# VM-MCU_v5_3.net
KiCad netlist of a schematic drawn in EAGLE
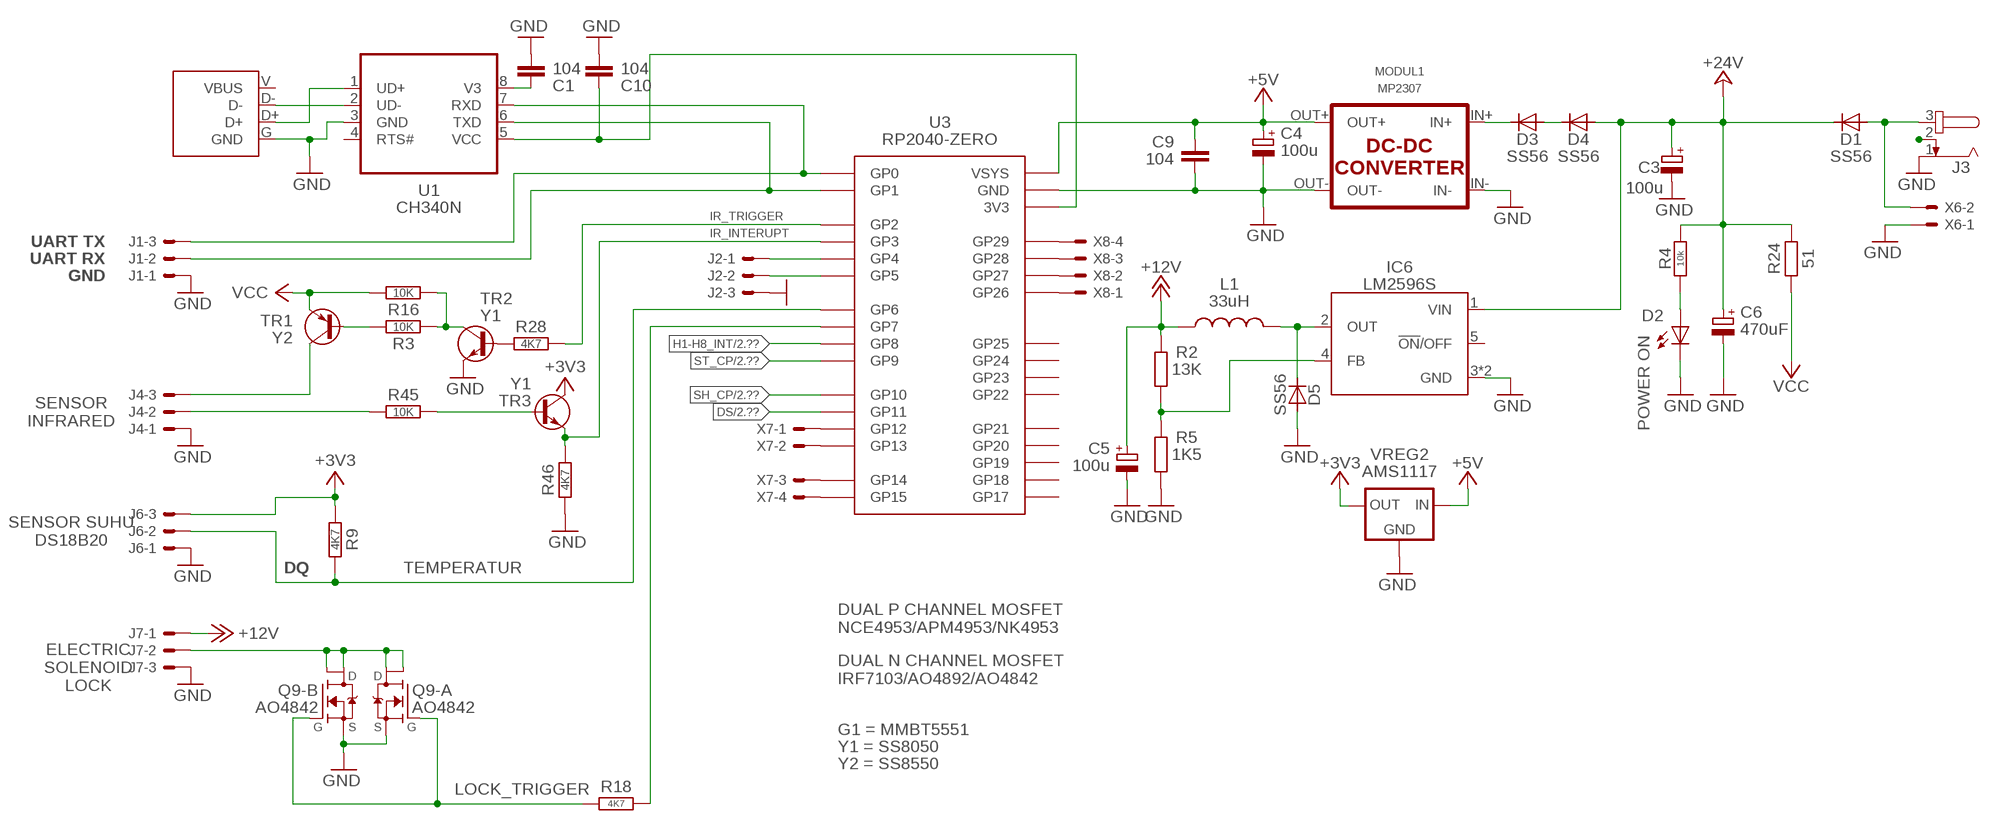
[diagram p0: schematic, sheet 1]
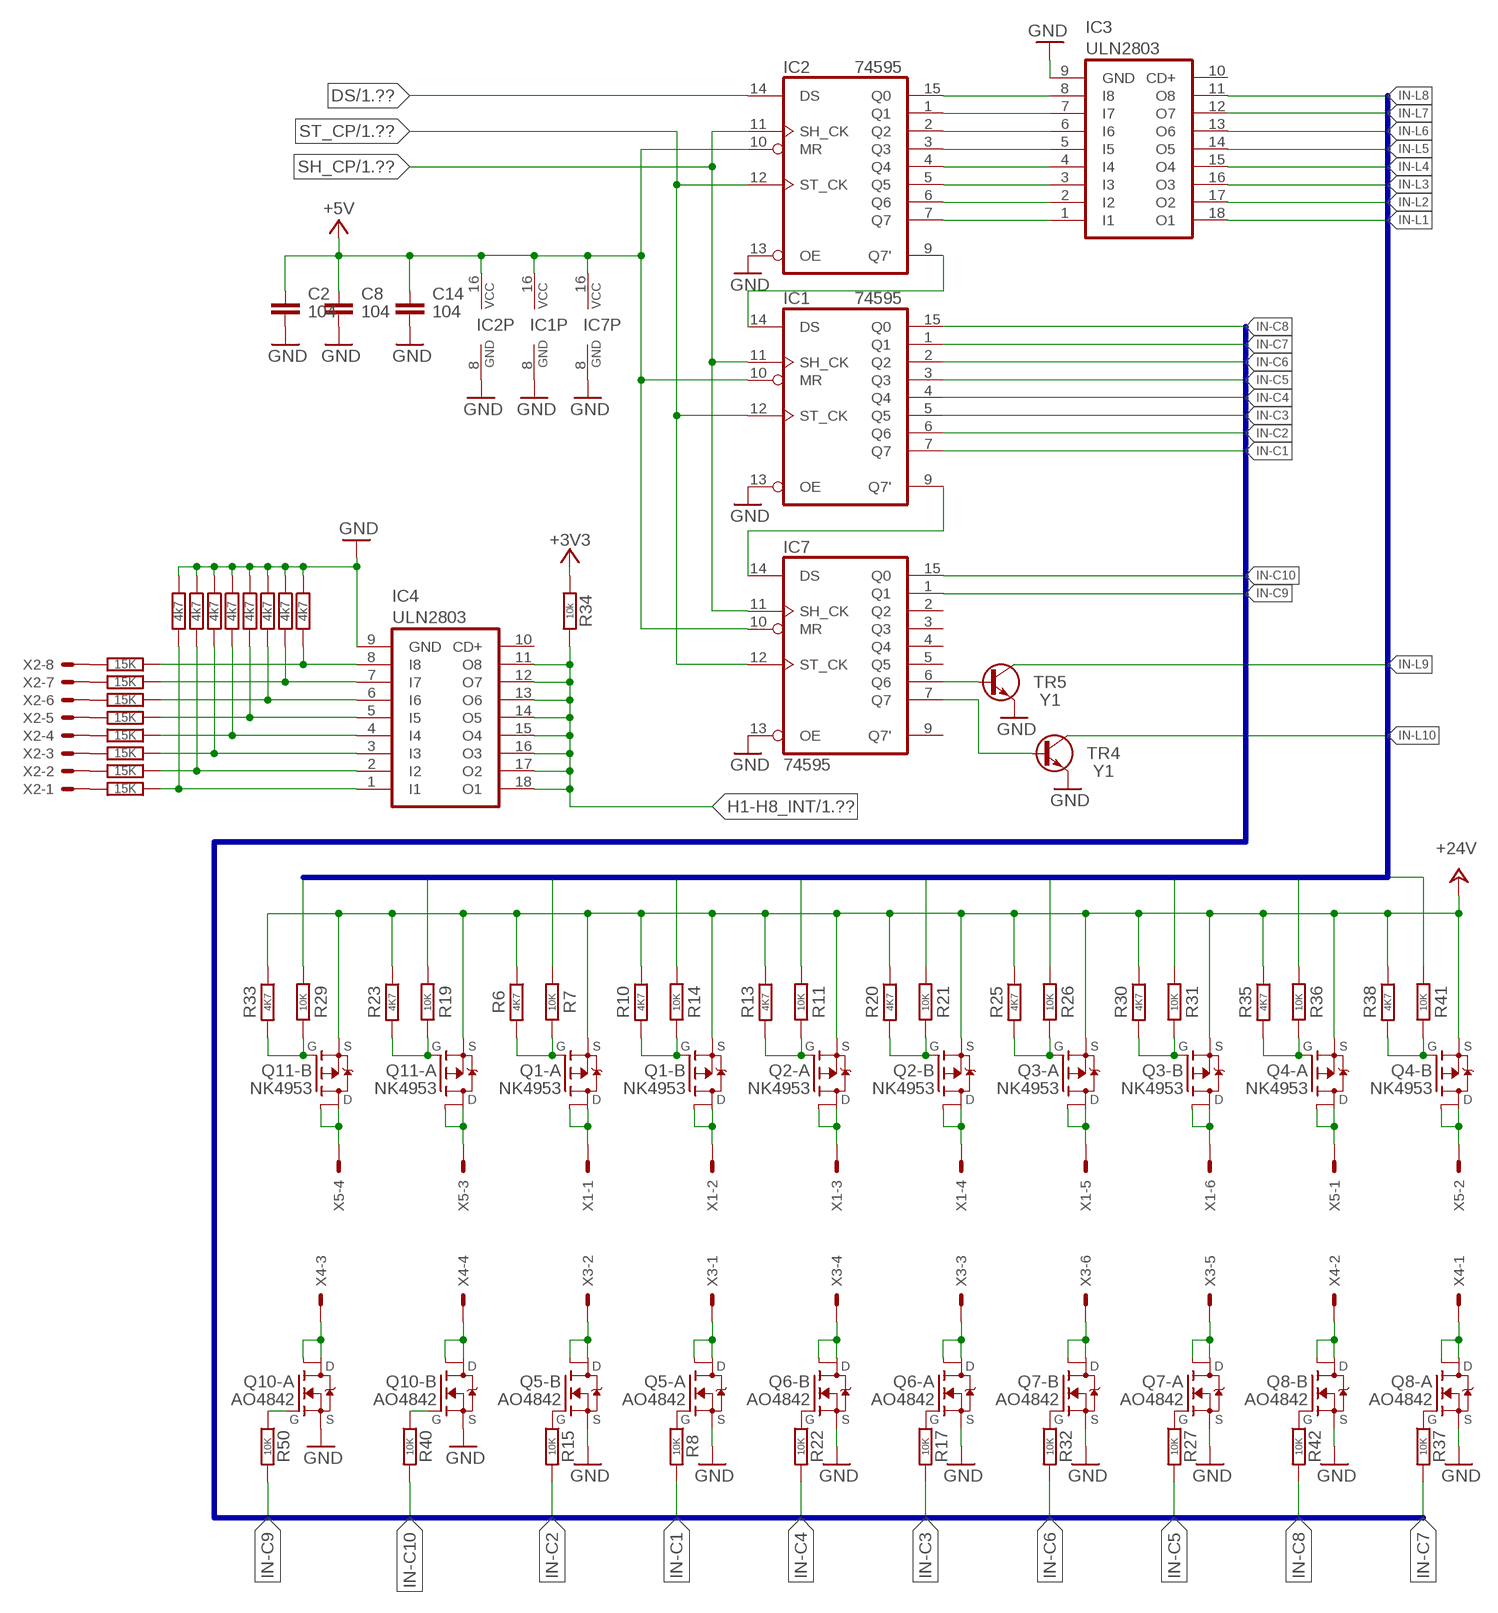
[diagram p1: schematic, sheet 2]

(export (version "E")
  (design (tool "Eeschema 10.0.6"))
  (components
    (comp (ref "C1")
      (value "104")
      (footprint "eagle-import:C1206")
      (libsource (lib "eagle-import") (part "CAP_SMD-C1206"))
    )
    (comp (ref "C3")
      (value "100u")
      (footprint "eagle-import:UD-6,3X7,7_NICHICON")
      (libsource (lib "eagle-import") (part "ELCO_UD-6,3X7,7"))
    )
    (comp (ref "C4")
      (value "100u")
      (footprint "eagle-import:UD-6,3X7,7_NICHICON")
      (libsource (lib "eagle-import") (part "ELCO_UD-6,3X7,7"))
    )
    (comp (ref "C5")
      (value "100u")
      (footprint "eagle-import:UD-6,3X7,7_NICHICON")
      (libsource (lib "eagle-import") (part "ELCO_UD-6,3X7,7"))
    )
    (comp (ref "C6")
      (value "470uF")
      (footprint "eagle-import:E5-10,5")
      (libsource (lib "eagle-import") (part "ELCO_E5-10.5"))
    )
    (comp (ref "C9")
      (value "104")
      (footprint "eagle-import:C1206")
      (libsource (lib "eagle-import") (part "CAP_SMD-C1206"))
    )
    (comp (ref "C10")
      (value "104")
      (footprint "eagle-import:C1206")
      (libsource (lib "eagle-import") (part "CAP_SMD-C1206"))
    )
    (comp (ref "D1")
      (value "SS56")
      (footprint "eagle-import:DO214AC")
      (libsource (lib "eagle-import") (part "DIODE_DO214AC"))
    )
    (comp (ref "D2")
      (value "POWER ON")
      (footprint "eagle-import:LED2835")
      (libsource (lib "eagle-import") (part "LED2835"))
    )
    (comp (ref "D3")
      (value "SS56")
      (footprint "eagle-import:DO214AC")
      (libsource (lib "eagle-import") (part "DIODE_DO214AC"))
    )
    (comp (ref "D4")
      (value "SS56")
      (footprint "eagle-import:DO214AC")
      (libsource (lib "eagle-import") (part "DIODE_DO214AC"))
    )
    (comp (ref "D5")
      (value "SS56")
      (footprint "eagle-import:DO214AC")
      (libsource (lib "eagle-import") (part "DIODE_DO214AC"))
    )
    (comp (ref "IC6")
      (value "LM2596S")
      (footprint "eagle-import:TO263-5")
      (fields (field (name "MF") "NATIONAL SEMICONDUCTOR") (field (name "MPN") "LM2596S-ADJ/NOPB"))
      (libsource (lib "eagle-import") (part "LM2596S"))
    )
    (comp (ref "J1")
      (value "SOKET-3P_KF2510-2.54")
      (footprint "eagle-import:KF2510-3P")
      (libsource (lib "eagle-import") (part "SOKET-3P_KF2510-2.54"))
    )
    (comp (ref "J2")
      (value "SOKET-3P_JST-XH-2.54")
      (footprint "eagle-import:3P-JST-XH")
      (libsource (lib "eagle-import") (part "SOKET-3P_JST-XH-2.54"))
    )
    (comp (ref "J3")
      (value "JACK-DC_5.5X2.1MM")
      (footprint "eagle-import:DC-5.5X2.1")
      (libsource (lib "eagle-import") (part "JACK-DC_5.5X2.1MM"))
    )
    (comp (ref "J4")
      (value "SOKET-3P_MOLEX-3.96")
      (footprint "eagle-import:3P-MOLEX")
      (fields (field (name "MF") "MOLEX"))
      (libsource (lib "eagle-import") (part "SOKET-3P_MOLEX-3.96"))
    )
    (comp (ref "J6")
      (value "SOKET-3P_KF2510-2.54")
      (footprint "eagle-import:KF2510-3P")
      (libsource (lib "eagle-import") (part "SOKET-3P_KF2510-2.54"))
    )
    (comp (ref "J7")
      (value "SOKET-3P_KF2510-2.54")
      (footprint "eagle-import:KF2510-3P")
      (libsource (lib "eagle-import") (part "SOKET-3P_KF2510-2.54"))
    )
    (comp (ref "L1")
      (value "33uH")
      (footprint "eagle-import:CDRH104")
      (libsource (lib "eagle-import") (part "INDUKTOR10X10"))
    )
    (comp (ref "MODUL1")
      (value "MP2307")
      (footprint "eagle-import:MP2307")
      (libsource (lib "eagle-import") (part "MINI360-MP2307MP2307-PTH"))
    )
    (comp (ref "Q9")
      (value "AO4842")
      (footprint "eagle-import:SO-8")
      (libsource (lib "eagle-import") (part "DUALFET-N_N+NAO4892"))
    )
    (comp (ref "R2")
      (value "13K")
      (footprint "eagle-import:R1206")
      (libsource (lib "eagle-import") (part "VM-MCU_RESISTOR_1206"))
    )
    (comp (ref "R3")
      (value "10K")
      (footprint "eagle-import:R1206")
      (libsource (lib "eagle-import") (part "VM-MCU_RESISTOR_1206"))
    )
    (comp (ref "R4")
      (value "10k")
      (footprint "eagle-import:R1206")
      (libsource (lib "eagle-import") (part "RESISTOR_1206"))
    )
    (comp (ref "R5")
      (value "1K5")
      (footprint "eagle-import:R1206")
      (libsource (lib "eagle-import") (part "VM-MCU_RESISTOR_1206"))
    )
    (comp (ref "R9")
      (value "4K7")
      (footprint "eagle-import:R1206")
      (libsource (lib "eagle-import") (part "VM-MCU_RESISTOR_1206"))
    )
    (comp (ref "R16")
      (value "10K")
      (footprint "eagle-import:R1206")
      (libsource (lib "eagle-import") (part "VM-MCU_RESISTOR_1206"))
    )
    (comp (ref "R18")
      (value "4K7")
      (footprint "eagle-import:R1206")
      (libsource (lib "eagle-import") (part "VM-MCU_RESISTOR_1206"))
    )
    (comp (ref "R24")
      (value "51")
      (footprint "eagle-import:R2512")
      (libsource (lib "eagle-import") (part "RESISTOR_2512"))
    )
    (comp (ref "R28")
      (value "4K7")
      (footprint "eagle-import:R1206")
      (libsource (lib "eagle-import") (part "VM-MCU_RESISTOR_1206"))
    )
    (comp (ref "R45")
      (value "10K")
      (footprint "eagle-import:R1206")
      (libsource (lib "eagle-import") (part "RESISTOR_1206"))
    )
    (comp (ref "R46")
      (value "4K7")
      (footprint "eagle-import:R1206")
      (libsource (lib "eagle-import") (part "VM-MCU_RESISTOR_1206"))
    )
    (comp (ref "TR1")
      (value "Y2")
      (footprint "eagle-import:SOT23-BEC")
      (libsource (lib "eagle-import") (part "BJT-PNP_SOT23-BCE"))
    )
    (comp (ref "TR2")
      (value "Y1")
      (footprint "eagle-import:SOT23-BEC")
      (libsource (lib "eagle-import") (part "BJT-NPN_SOT23-BEC"))
    )
    (comp (ref "TR3")
      (value "Y1")
      (footprint "eagle-import:SOT23-BEC")
      (libsource (lib "eagle-import") (part "BJT-NPN_SOT23-BEC"))
    )
    (comp (ref "U$3")
      (value "USB-C_BREAKOUT_")
      (footprint "eagle-import:USB-C_4P")
      (libsource (lib "eagle-import") (part "USB-C_BREAKOUT_"))
    )
    (comp (ref "U1")
      (value "CH340N")
      (footprint "eagle-import:SO-8")
      (libsource (lib "eagle-import") (part "CH340N"))
    )
    (comp (ref "U3")
      (value "RP2040-ZERO")
      (footprint "eagle-import:PICO-ZERO")
      (libsource (lib "eagle-import") (part "RASPBERRY-PICO-ZERO_"))
    )
    (comp (ref "VREG2")
      (value "AMS1117")
      (footprint "eagle-import:SOT223")
      (libsource (lib "eagle-import") (part "78XXX_SOT223"))
    )
    (comp (ref "X6")
      (value "SOKET-2P_MOLEX-3.96")
      (footprint "eagle-import:2P-MOLEX")
      (fields (field (name "MF") "MOLEX"))
      (libsource (lib "eagle-import") (part "SOKET-2P_MOLEX-3.96"))
    )
    (comp (ref "X7")
      (value "SOKET-4P_JST-XH-2.54")
      (footprint "eagle-import:4P-JST-XH")
      (libsource (lib "eagle-import") (part "SOKET-4P_JST-XH-2.54"))
    )
    (comp (ref "X8")
      (value "SOKET-4P_JST-XH-2.54")
      (footprint "eagle-import:4P-JST-XH")
      (libsource (lib "eagle-import") (part "SOKET-4P_JST-XH-2.54"))
    )
    (comp (ref "C2")
      (value "104")
      (footprint "eagle-import:C1206")
      (libsource (lib "eagle-import") (part "CAP_SMD-C1206"))
    )
    (comp (ref "C8")
      (value "104")
      (footprint "eagle-import:C1206")
      (libsource (lib "eagle-import") (part "CAP_SMD-C1206"))
    )
    (comp (ref "C14")
      (value "104")
      (footprint "eagle-import:C1206")
      (libsource (lib "eagle-import") (part "CAP_SMD-C1206"))
    )
    (comp (ref "IC1")
      (value "74595")
      (footprint "eagle-import:SO16")
      (libsource (lib "eagle-import") (part "74595"))
    )
    (comp (ref "IC2")
      (value "74595")
      (footprint "eagle-import:SO16")
      (libsource (lib "eagle-import") (part "74595"))
    )
    (comp (ref "IC3")
      (value "ULN2803")
      (footprint "eagle-import:SO18W")
      (libsource (lib "eagle-import") (part "ULN2805ASO18"))
    )
    (comp (ref "IC4")
      (value "ULN2803")
      (footprint "eagle-import:SO18W")
      (libsource (lib "eagle-import") (part "ULN2805ASO18"))
    )
    (comp (ref "IC7")
      (value "74595")
      (footprint "eagle-import:SO16")
      (libsource (lib "eagle-import") (part "74595"))
    )
    (comp (ref "Q1")
      (value "NK4953")
      (footprint "eagle-import:SO-8")
      (libsource (lib "eagle-import") (part "DUALFET-P_P+PNCE4953"))
    )
    (comp (ref "Q2")
      (value "NK4953")
      (footprint "eagle-import:SO-8")
      (libsource (lib "eagle-import") (part "DUALFET-P_P+PNCE4953"))
    )
    (comp (ref "Q3")
      (value "NK4953")
      (footprint "eagle-import:SO-8")
      (libsource (lib "eagle-import") (part "DUALFET-P_P+PNCE4953"))
    )
    (comp (ref "Q4")
      (value "NK4953")
      (footprint "eagle-import:SO-8")
      (libsource (lib "eagle-import") (part "DUALFET-P_P+PNCE4953"))
    )
    (comp (ref "Q5")
      (value "AO4842")
      (footprint "eagle-import:SO-8")
      (libsource (lib "eagle-import") (part "DUALFET-N_N+NAO4892"))
    )
    (comp (ref "Q6")
      (value "AO4842")
      (footprint "eagle-import:SO-8")
      (libsource (lib "eagle-import") (part "DUALFET-N_N+NAO4892"))
    )
    (comp (ref "Q7")
      (value "AO4842")
      (footprint "eagle-import:SO-8")
      (libsource (lib "eagle-import") (part "DUALFET-N_N+NAO4892"))
    )
    (comp (ref "Q8")
      (value "AO4842")
      (footprint "eagle-import:SO-8")
      (libsource (lib "eagle-import") (part "DUALFET-N_N+NAO4892"))
    )
    (comp (ref "Q10")
      (value "AO4842")
      (footprint "eagle-import:SO-8")
      (libsource (lib "eagle-import") (part "DUALFET-N_N+NAO4892"))
    )
    (comp (ref "Q11")
      (value "NK4953")
      (footprint "eagle-import:SO-8")
      (libsource (lib "eagle-import") (part "DUALFET-P_P+PNCE4953"))
    )
    (comp (ref "R1")
      (value "15K")
      (footprint "eagle-import:R0805")
      (libsource (lib "eagle-import") (part "RESISTOR_0805"))
    )
    (comp (ref "R6")
      (value "4K7")
      (footprint "eagle-import:R1206")
      (libsource (lib "eagle-import") (part "RESISTOR_1206"))
    )
    (comp (ref "R7")
      (value "10K")
      (footprint "eagle-import:R1206")
      (libsource (lib "eagle-import") (part "RESISTOR_1206"))
    )
    (comp (ref "R8")
      (value "10K")
      (footprint "eagle-import:R1206")
      (libsource (lib "eagle-import") (part "RESISTOR_1206"))
    )
    (comp (ref "R10")
      (value "4K7")
      (footprint "eagle-import:R1206")
      (libsource (lib "eagle-import") (part "RESISTOR_1206"))
    )
    (comp (ref "R11")
      (value "10K")
      (footprint "eagle-import:R1206")
      (libsource (lib "eagle-import") (part "RESISTOR_1206"))
    )
    (comp (ref "R12")
      (value "15K")
      (footprint "eagle-import:R0805")
      (libsource (lib "eagle-import") (part "RESISTOR_0805"))
    )
    (comp (ref "R13")
      (value "4K7")
      (footprint "eagle-import:R1206")
      (libsource (lib "eagle-import") (part "RESISTOR_1206"))
    )
    (comp (ref "R14")
      (value "10K")
      (footprint "eagle-import:R1206")
      (libsource (lib "eagle-import") (part "RESISTOR_1206"))
    )
    (comp (ref "R15")
      (value "10K")
      (footprint "eagle-import:R1206")
      (libsource (lib "eagle-import") (part "RESISTOR_1206"))
    )
    (comp (ref "R17")
      (value "10K")
      (footprint "eagle-import:R1206")
      (libsource (lib "eagle-import") (part "RESISTOR_1206"))
    )
    (comp (ref "R19")
      (value "10K")
      (footprint "eagle-import:R1206")
      (libsource (lib "eagle-import") (part "RESISTOR_1206"))
    )
    (comp (ref "R20")
      (value "4K7")
      (footprint "eagle-import:R1206")
      (libsource (lib "eagle-import") (part "RESISTOR_1206"))
    )
    (comp (ref "R21")
      (value "10K")
      (footprint "eagle-import:R1206")
      (libsource (lib "eagle-import") (part "RESISTOR_1206"))
    )
    (comp (ref "R22")
      (value "10K")
      (footprint "eagle-import:R1206")
      (libsource (lib "eagle-import") (part "RESISTOR_1206"))
    )
    (comp (ref "R23")
      (value "4K7")
      (footprint "eagle-import:R1206")
      (libsource (lib "eagle-import") (part "RESISTOR_1206"))
    )
    (comp (ref "R25")
      (value "4K7")
      (footprint "eagle-import:R1206")
      (libsource (lib "eagle-import") (part "RESISTOR_1206"))
    )
    (comp (ref "R26")
      (value "10K")
      (footprint "eagle-import:R1206")
      (libsource (lib "eagle-import") (part "RESISTOR_1206"))
    )
    (comp (ref "R27")
      (value "10K")
      (footprint "eagle-import:R1206")
      (libsource (lib "eagle-import") (part "RESISTOR_1206"))
    )
    (comp (ref "R29")
      (value "10K")
      (footprint "eagle-import:R1206")
      (libsource (lib "eagle-import") (part "RESISTOR_1206"))
    )
    (comp (ref "R30")
      (value "4K7")
      (footprint "eagle-import:R1206")
      (libsource (lib "eagle-import") (part "RESISTOR_1206"))
    )
    (comp (ref "R31")
      (value "10K")
      (footprint "eagle-import:R1206")
      (libsource (lib "eagle-import") (part "RESISTOR_1206"))
    )
    (comp (ref "R32")
      (value "10K")
      (footprint "eagle-import:R1206")
      (libsource (lib "eagle-import") (part "RESISTOR_1206"))
    )
    (comp (ref "R33")
      (value "4K7")
      (footprint "eagle-import:R1206")
      (libsource (lib "eagle-import") (part "RESISTOR_1206"))
    )
    (comp (ref "R34")
      (value "10k")
      (footprint "eagle-import:R1206")
      (libsource (lib "eagle-import") (part "RESISTOR_1206"))
    )
    (comp (ref "R35")
      (value "4K7")
      (footprint "eagle-import:R1206")
      (libsource (lib "eagle-import") (part "RESISTOR_1206"))
    )
    (comp (ref "R36")
      (value "10K")
      (footprint "eagle-import:R1206")
      (libsource (lib "eagle-import") (part "RESISTOR_1206"))
    )
    (comp (ref "R37")
      (value "10K")
      (footprint "eagle-import:R1206")
      (libsource (lib "eagle-import") (part "RESISTOR_1206"))
    )
    (comp (ref "R38")
      (value "4K7")
      (footprint "eagle-import:R1206")
      (libsource (lib "eagle-import") (part "RESISTOR_1206"))
    )
    (comp (ref "R39")
      (value "15K")
      (footprint "eagle-import:R0805")
      (libsource (lib "eagle-import") (part "RESISTOR_0805"))
    )
    (comp (ref "R40")
      (value "10K")
      (footprint "eagle-import:R1206")
      (libsource (lib "eagle-import") (part "RESISTOR_1206"))
    )
    (comp (ref "R41")
      (value "10K")
      (footprint "eagle-import:R1206")
      (libsource (lib "eagle-import") (part "RESISTOR_1206"))
    )
    (comp (ref "R42")
      (value "10K")
      (footprint "eagle-import:R1206")
      (libsource (lib "eagle-import") (part "RESISTOR_1206"))
    )
    (comp (ref "R43")
      (value "15K")
      (footprint "eagle-import:R0805")
      (libsource (lib "eagle-import") (part "RESISTOR_0805"))
    )
    (comp (ref "R44")
      (value "15K")
      (footprint "eagle-import:R0805")
      (libsource (lib "eagle-import") (part "RESISTOR_0805"))
    )
    (comp (ref "R47")
      (value "15K")
      (footprint "eagle-import:R0805")
      (libsource (lib "eagle-import") (part "RESISTOR_0805"))
    )
    (comp (ref "R48")
      (value "15K")
      (footprint "eagle-import:R0805")
      (libsource (lib "eagle-import") (part "RESISTOR_0805"))
    )
    (comp (ref "R49")
      (value "15K")
      (footprint "eagle-import:R0805")
      (libsource (lib "eagle-import") (part "RESISTOR_0805"))
    )
    (comp (ref "R50")
      (value "10K")
      (footprint "eagle-import:R1206")
      (libsource (lib "eagle-import") (part "RESISTOR_1206"))
    )
    (comp (ref "R51")
      (value "4k7")
      (footprint "eagle-import:R0805")
      (libsource (lib "eagle-import") (part "RESISTOR_0805"))
    )
    (comp (ref "R52")
      (value "4k7")
      (footprint "eagle-import:R0805")
      (libsource (lib "eagle-import") (part "RESISTOR_0805"))
    )
    (comp (ref "R53")
      (value "4k7")
      (footprint "eagle-import:R0805")
      (libsource (lib "eagle-import") (part "RESISTOR_0805"))
    )
    (comp (ref "R54")
      (value "4k7")
      (footprint "eagle-import:R0805")
      (libsource (lib "eagle-import") (part "RESISTOR_0805"))
    )
    (comp (ref "R55")
      (value "4k7")
      (footprint "eagle-import:R0805")
      (libsource (lib "eagle-import") (part "RESISTOR_0805"))
    )
    (comp (ref "R56")
      (value "4k7")
      (footprint "eagle-import:R0805")
      (libsource (lib "eagle-import") (part "RESISTOR_0805"))
    )
    (comp (ref "R57")
      (value "4k7")
      (footprint "eagle-import:R0805")
      (libsource (lib "eagle-import") (part "RESISTOR_0805"))
    )
    (comp (ref "R58")
      (value "4k7")
      (footprint "eagle-import:R0805")
      (libsource (lib "eagle-import") (part "RESISTOR_0805"))
    )
    (comp (ref "TR4")
      (value "Y1")
      (footprint "eagle-import:SOT23-BEC")
      (libsource (lib "eagle-import") (part "BJT-NPN_SOT23-BEC"))
    )
    (comp (ref "TR5")
      (value "Y1")
      (footprint "eagle-import:SOT23-BEC")
      (libsource (lib "eagle-import") (part "BJT-NPN_SOT23-BEC"))
    )
    (comp (ref "X1")
      (value "SOKET-6P_MOLEX-3.96")
      (footprint "eagle-import:6P-MOLEX")
      (fields (field (name "MF") "MOLEX"))
      (libsource (lib "eagle-import") (part "SOKET-6P_MOLEX-3.96"))
    )
    (comp (ref "X2")
      (value "SOKET-8P_MOLEX-3.96")
      (footprint "eagle-import:8P-MOLEX")
      (fields (field (name "MF") "MOLEX"))
      (libsource (lib "eagle-import") (part "SOKET-8P_MOLEX-3.96"))
    )
    (comp (ref "X3")
      (value "SOKET-6P_MOLEX-3.96")
      (footprint "eagle-import:6P-MOLEX")
      (fields (field (name "MF") "MOLEX"))
      (libsource (lib "eagle-import") (part "SOKET-6P_MOLEX-3.96"))
    )
    (comp (ref "X4")
      (value "SOKET-4P_MOLEX-3.96")
      (footprint "eagle-import:4P-MOLEX")
      (fields (field (name "MF") "MOLEX"))
      (libsource (lib "eagle-import") (part "SOKET-4P_MOLEX-3.96"))
    )
    (comp (ref "X5")
      (value "SOKET-4P_MOLEX-3.96")
      (footprint "eagle-import:4P-MOLEX")
      (fields (field (name "MF") "MOLEX"))
      (libsource (lib "eagle-import") (part "SOKET-4P_MOLEX-3.96"))
    )
  )
  (nets
    (net (code "1") (name "+3V3") (class "Default")
      (node (ref "J6") (pin "3") (pinfunction "S_3") (pintype "passive"))
      (node (ref "R34") (pin "2") (pinfunction "2_2") (pintype "passive"))
      (node (ref "R9") (pin "1") (pinfunction "1_1") (pintype "passive"))
      (node (ref "TR3") (pin "C") (pinfunction "C_C") (pintype "passive"))
      (node (ref "VREG2") (pin "4") (pinfunction "OUT_4") (pintype "passive"))
    )
    (net (code "2") (name "+5V") (class "Default")
      (node (ref "C14") (pin "1") (pinfunction "1_1") (pintype "passive"))
      (node (ref "C2") (pin "1") (pinfunction "1_1") (pintype "passive"))
      (node (ref "C4") (pin "+") (pinfunction "+_+") (pintype "passive"))
      (node (ref "C8") (pin "1") (pinfunction "1_1") (pintype "passive"))
      (node (ref "C9") (pin "1") (pinfunction "1_1") (pintype "passive"))
      (node (ref "IC1") (pin "10") (pinfunction "MR_10") (pintype "input"))
      (node (ref "IC1") (pin "16") (pinfunction "VCC_16") (pintype "power_in"))
      (node (ref "IC2") (pin "10") (pinfunction "MR_10") (pintype "input"))
      (node (ref "IC2") (pin "16") (pinfunction "VCC_16") (pintype "power_in"))
      (node (ref "IC7") (pin "10") (pinfunction "MR_10") (pintype "input"))
      (node (ref "IC7") (pin "16") (pinfunction "VCC_16") (pintype "power_in"))
      (node (ref "MODUL1") (pin "OUT+") (pinfunction "OUT+_OUT+") (pintype "bidirectional"))
      (node (ref "U3") (pin "5V") (pinfunction "VSYS_5V") (pintype "power_in"))
      (node (ref "VREG2") (pin "3") (pinfunction "IN_3") (pintype "input"))
    )
    (net (code "3") (name "+12V") (class "Default")
      (node (ref "C5") (pin "+") (pinfunction "+_+") (pintype "passive"))
      (node (ref "J7") (pin "1") (pinfunction "S_1") (pintype "passive"))
      (node (ref "L1") (pin "1") (pinfunction "1_1") (pintype "passive"))
      (node (ref "R2") (pin "1") (pinfunction "1_1") (pintype "passive"))
    )
    (net (code "4") (name "+24V") (class "Default")
      (node (ref "C3") (pin "+") (pinfunction "+_+") (pintype "passive"))
      (node (ref "C6") (pin "+") (pinfunction "+_+") (pintype "passive"))
      (node (ref "D1") (pin "C") (pinfunction "C_C") (pintype "passive"))
      (node (ref "D4") (pin "A") (pinfunction "A_A") (pintype "passive"))
      (node (ref "IC6") (pin "1") (pinfunction "VIN_1") (pintype "input"))
      (node (ref "Q1") (pin "1") (pinfunction "S_1") (pintype "passive"))
      (node (ref "Q1") (pin "3") (pinfunction "S_3") (pintype "passive"))
      (node (ref "Q11") (pin "1") (pinfunction "S_1") (pintype "passive"))
      (node (ref "Q11") (pin "3") (pinfunction "S_3") (pintype "passive"))
      (node (ref "Q2") (pin "1") (pinfunction "S_1") (pintype "passive"))
      (node (ref "Q2") (pin "3") (pinfunction "S_3") (pintype "passive"))
      (node (ref "Q3") (pin "1") (pinfunction "S_1") (pintype "passive"))
      (node (ref "Q3") (pin "3") (pinfunction "S_3") (pintype "passive"))
      (node (ref "Q4") (pin "1") (pinfunction "S_1") (pintype "passive"))
      (node (ref "Q4") (pin "3") (pinfunction "S_3") (pintype "passive"))
      (node (ref "R10") (pin "1") (pinfunction "1_1") (pintype "passive"))
      (node (ref "R13") (pin "1") (pinfunction "1_1") (pintype "passive"))
      (node (ref "R20") (pin "1") (pinfunction "1_1") (pintype "passive"))
      (node (ref "R23") (pin "1") (pinfunction "1_1") (pintype "passive"))
      (node (ref "R24") (pin "2") (pinfunction "2_2") (pintype "passive"))
      (node (ref "R25") (pin "1") (pinfunction "1_1") (pintype "passive"))
      (node (ref "R30") (pin "1") (pinfunction "1_1") (pintype "passive"))
      (node (ref "R33") (pin "1") (pinfunction "1_1") (pintype "passive"))
      (node (ref "R35") (pin "1") (pinfunction "1_1") (pintype "passive"))
      (node (ref "R38") (pin "1") (pinfunction "1_1") (pintype "passive"))
      (node (ref "R4") (pin "2") (pinfunction "2_2") (pintype "passive"))
      (node (ref "R6") (pin "1") (pinfunction "1_1") (pintype "passive"))
    )
    (net (code "5") (name "DS") (class "Default")
      (node (ref "IC2") (pin "14") (pinfunction "DS_14") (pintype "input"))
      (node (ref "U3") (pin "P11") (pinfunction "GP11_P11") (pintype "bidirectional"))
    )
    (net (code "6") (name "GND") (class "Default")
      (node (ref "C1") (pin "2") (pinfunction "2_2") (pintype "passive"))
      (node (ref "C10") (pin "2") (pinfunction "2_2") (pintype "passive"))
      (node (ref "C14") (pin "2") (pinfunction "2_2") (pintype "passive"))
      (node (ref "C2") (pin "2") (pinfunction "2_2") (pintype "passive"))
      (node (ref "C3") (pin "-") (pinfunction "-_-") (pintype "passive"))
      (node (ref "C4") (pin "-") (pinfunction "-_-") (pintype "passive"))
      (node (ref "C5") (pin "-") (pinfunction "-_-") (pintype "passive"))
      (node (ref "C6") (pin "-") (pinfunction "-_-") (pintype "passive"))
      (node (ref "C8") (pin "2") (pinfunction "2_2") (pintype "passive"))
      (node (ref "C9") (pin "2") (pinfunction "2_2") (pintype "passive"))
      (node (ref "D2") (pin "C") (pinfunction "C_C") (pintype "passive"))
      (node (ref "D5") (pin "A") (pinfunction "A_A") (pintype "passive"))
      (node (ref "IC1") (pin "13") (pinfunction "OE_13") (pintype "input"))
      (node (ref "IC1") (pin "8") (pinfunction "GND_8") (pintype "power_in"))
      (node (ref "IC2") (pin "13") (pinfunction "OE_13") (pintype "input"))
      (node (ref "IC2") (pin "8") (pinfunction "GND_8") (pintype "power_in"))
      (node (ref "IC3") (pin "9") (pinfunction "GND_9") (pintype "power_in"))
      (node (ref "IC4") (pin "9") (pinfunction "GND_9") (pintype "power_in"))
      (node (ref "IC6") (pin "3") (pinfunction "GND_3") (pintype "power_in"))
      (node (ref "IC6") (pin "6") (pinfunction "GND_6") (pintype "power_in"))
      (node (ref "IC7") (pin "13") (pinfunction "OE_13") (pintype "input"))
      (node (ref "IC7") (pin "8") (pinfunction "GND_8") (pintype "power_in"))
      (node (ref "J1") (pin "1") (pinfunction "S_1") (pintype "passive"))
      (node (ref "J2") (pin "3") (pinfunction "S_3") (pintype "passive"))
      (node (ref "J3") (pin "1") (pinfunction "1_1") (pintype "passive"))
      (node (ref "J4") (pin "1") (pinfunction "S_1") (pintype "passive"))
      (node (ref "J6") (pin "1") (pinfunction "S_1") (pintype "passive"))
      (node (ref "J7") (pin "3") (pinfunction "S_3") (pintype "passive"))
      (node (ref "MODUL1") (pin "IN-") (pinfunction "IN-_IN-") (pintype "bidirectional"))
      (node (ref "MODUL1") (pin "OUT-") (pinfunction "OUT-_OUT-") (pintype "bidirectional"))
      (node (ref "Q10") (pin "1") (pinfunction "S_1") (pintype "passive"))
      (node (ref "Q10") (pin "3") (pinfunction "S_3") (pintype "passive"))
      (node (ref "Q5") (pin "1") (pinfunction "S_1") (pintype "passive"))
      (node (ref "Q5") (pin "3") (pinfunction "S_3") (pintype "passive"))
      (node (ref "Q6") (pin "1") (pinfunction "S_1") (pintype "passive"))
      (node (ref "Q6") (pin "3") (pinfunction "S_3") (pintype "passive"))
      (node (ref "Q7") (pin "1") (pinfunction "S_1") (pintype "passive"))
      (node (ref "Q7") (pin "3") (pinfunction "S_3") (pintype "passive"))
      (node (ref "Q8") (pin "1") (pinfunction "S_1") (pintype "passive"))
      (node (ref "Q8") (pin "3") (pinfunction "S_3") (pintype "passive"))
      (node (ref "Q9") (pin "1") (pinfunction "S_1") (pintype "passive"))
      (node (ref "Q9") (pin "3") (pinfunction "S_3") (pintype "passive"))
      (node (ref "R46") (pin "1") (pinfunction "1_1") (pintype "passive"))
      (node (ref "R5") (pin "2") (pinfunction "2_2") (pintype "passive"))
      (node (ref "R51") (pin "1") (pinfunction "1_1") (pintype "passive"))
      (node (ref "R52") (pin "1") (pinfunction "1_1") (pintype "passive"))
      (node (ref "R53") (pin "1") (pinfunction "1_1") (pintype "passive"))
      (node (ref "R54") (pin "1") (pinfunction "1_1") (pintype "passive"))
      (node (ref "R55") (pin "1") (pinfunction "1_1") (pintype "passive"))
      (node (ref "R56") (pin "1") (pinfunction "1_1") (pintype "passive"))
      (node (ref "R57") (pin "1") (pinfunction "1_1") (pintype "passive"))
      (node (ref "R58") (pin "1") (pinfunction "1_1") (pintype "passive"))
      (node (ref "TR2") (pin "E") (pinfunction "E_E") (pintype "passive"))
      (node (ref "TR4") (pin "E") (pinfunction "E_E") (pintype "passive"))
      (node (ref "TR5") (pin "E") (pinfunction "E_E") (pintype "passive"))
      (node (ref "U$3") (pin "G") (pinfunction "GND_G") (pintype "bidirectional"))
      (node (ref "U1") (pin "3") (pinfunction "GND_3") (pintype "power_in"))
      (node (ref "U3") (pin "G") (pinfunction "GND_G") (pintype "power_in"))
      (node (ref "VREG2") (pin "1") (pinfunction "GND_1") (pintype "input"))
      (node (ref "X6") (pin "1") (pinfunction "S_1") (pintype "passive"))
    )
    (net (code "7") (name "H1-H8_INT") (class "Default")
      (node (ref "IC4") (pin "11") (pinfunction "O8_11") (pintype "open_collector"))
      (node (ref "IC4") (pin "12") (pinfunction "O7_12") (pintype "open_collector"))
      (node (ref "IC4") (pin "13") (pinfunction "O6_13") (pintype "open_collector"))
      (node (ref "IC4") (pin "14") (pinfunction "O5_14") (pintype "open_collector"))
      (node (ref "IC4") (pin "15") (pinfunction "O4_15") (pintype "open_collector"))
      (node (ref "IC4") (pin "16") (pinfunction "O3_16") (pintype "open_collector"))
      (node (ref "IC4") (pin "17") (pinfunction "O2_17") (pintype "open_collector"))
      (node (ref "IC4") (pin "18") (pinfunction "O1_18") (pintype "open_collector"))
      (node (ref "R34") (pin "1") (pinfunction "1_1") (pintype "passive"))
      (node (ref "U3") (pin "P8") (pinfunction "GP8_P8") (pintype "bidirectional"))
    )
    (net (code "8") (name "IN-C1") (class "Default")
      (node (ref "IC1") (pin "7") (pinfunction "Q7_7") (pintype "tri_state"))
      (node (ref "R8") (pin "2") (pinfunction "2_2") (pintype "passive"))
    )
    (net (code "9") (name "IN-C2") (class "Default")
      (node (ref "IC1") (pin "6") (pinfunction "Q6_6") (pintype "tri_state"))
      (node (ref "R15") (pin "2") (pinfunction "2_2") (pintype "passive"))
    )
    (net (code "10") (name "IN-C3") (class "Default")
      (node (ref "IC1") (pin "5") (pinfunction "Q5_5") (pintype "tri_state"))
      (node (ref "R17") (pin "2") (pinfunction "2_2") (pintype "passive"))
    )
    (net (code "11") (name "IN-C4") (class "Default")
      (node (ref "IC1") (pin "4") (pinfunction "Q4_4") (pintype "tri_state"))
      (node (ref "R22") (pin "2") (pinfunction "2_2") (pintype "passive"))
    )
    (net (code "12") (name "IN-C5") (class "Default")
      (node (ref "IC1") (pin "3") (pinfunction "Q3_3") (pintype "tri_state"))
      (node (ref "R27") (pin "2") (pinfunction "2_2") (pintype "passive"))
    )
    (net (code "13") (name "IN-C6") (class "Default")
      (node (ref "IC1") (pin "2") (pinfunction "Q2_2") (pintype "tri_state"))
      (node (ref "R32") (pin "2") (pinfunction "2_2") (pintype "passive"))
    )
    (net (code "14") (name "IN-C7") (class "Default")
      (node (ref "IC1") (pin "1") (pinfunction "Q1_1") (pintype "tri_state"))
      (node (ref "R37") (pin "2") (pinfunction "2_2") (pintype "passive"))
    )
    (net (code "15") (name "IN-C8") (class "Default")
      (node (ref "IC1") (pin "15") (pinfunction "Q0_15") (pintype "tri_state"))
      (node (ref "R42") (pin "2") (pinfunction "2_2") (pintype "passive"))
    )
    (net (code "16") (name "IN-C9") (class "Default")
      (node (ref "IC7") (pin "1") (pinfunction "Q1_1") (pintype "tri_state"))
      (node (ref "R50") (pin "2") (pinfunction "2_2") (pintype "passive"))
    )
    (net (code "17") (name "IN-C10") (class "Default")
      (node (ref "IC7") (pin "15") (pinfunction "Q0_15") (pintype "tri_state"))
      (node (ref "R40") (pin "2") (pinfunction "2_2") (pintype "passive"))
    )
    (net (code "18") (name "IN-L1") (class "Default")
      (node (ref "IC3") (pin "18") (pinfunction "O1_18") (pintype "open_collector"))
      (node (ref "R7") (pin "2") (pinfunction "2_2") (pintype "passive"))
    )
    (net (code "19") (name "IN-L2") (class "Default")
      (node (ref "IC3") (pin "17") (pinfunction "O2_17") (pintype "open_collector"))
      (node (ref "R14") (pin "2") (pinfunction "2_2") (pintype "passive"))
    )
    (net (code "20") (name "IN-L3") (class "Default")
      (node (ref "IC3") (pin "16") (pinfunction "O3_16") (pintype "open_collector"))
      (node (ref "R11") (pin "2") (pinfunction "2_2") (pintype "passive"))
    )
    (net (code "21") (name "IN-L4") (class "Default")
      (node (ref "IC3") (pin "15") (pinfunction "O4_15") (pintype "open_collector"))
      (node (ref "R21") (pin "2") (pinfunction "2_2") (pintype "passive"))
    )
    (net (code "22") (name "IN-L5") (class "Default")
      (node (ref "IC3") (pin "14") (pinfunction "O5_14") (pintype "open_collector"))
      (node (ref "R26") (pin "2") (pinfunction "2_2") (pintype "passive"))
    )
    (net (code "23") (name "IN-L6") (class "Default")
      (node (ref "IC3") (pin "13") (pinfunction "O6_13") (pintype "open_collector"))
      (node (ref "R31") (pin "2") (pinfunction "2_2") (pintype "passive"))
    )
    (net (code "24") (name "IN-L7") (class "Default")
      (node (ref "IC3") (pin "12") (pinfunction "O7_12") (pintype "open_collector"))
      (node (ref "R36") (pin "2") (pinfunction "2_2") (pintype "passive"))
    )
    (net (code "25") (name "IN-L8") (class "Default")
      (node (ref "IC3") (pin "11") (pinfunction "O8_11") (pintype "open_collector"))
      (node (ref "R41") (pin "2") (pinfunction "2_2") (pintype "passive"))
    )
    (net (code "26") (name "IN-L9") (class "Default")
      (node (ref "R19") (pin "2") (pinfunction "2_2") (pintype "passive"))
      (node (ref "TR5") (pin "C") (pinfunction "C_C") (pintype "passive"))
    )
    (net (code "27") (name "IN-L10") (class "Default")
      (node (ref "R29") (pin "2") (pinfunction "2_2") (pintype "passive"))
      (node (ref "TR4") (pin "C") (pinfunction "C_C") (pintype "passive"))
    )
    (net (code "28") (name "Net-(D2-PadA)") (class "Default")
      (node (ref "D2") (pin "A") (pinfunction "A_A") (pintype "passive"))
      (node (ref "R4") (pin "1") (pinfunction "1_1") (pintype "passive"))
    )
    (net (code "29") (name "Net-(D3-PadA)") (class "Default")
      (node (ref "D3") (pin "A") (pinfunction "A_A") (pintype "passive"))
      (node (ref "D4") (pin "C") (pinfunction "C_C") (pintype "passive"))
    )
    (net (code "30") (name "Net-(D3-PadC)") (class "Default")
      (node (ref "D3") (pin "C") (pinfunction "C_C") (pintype "passive"))
      (node (ref "MODUL1") (pin "IN+") (pinfunction "IN+_IN+") (pintype "bidirectional"))
    )
    (net (code "31") (name "Net-(IC1A-DS)") (class "Default")
      (node (ref "IC1") (pin "14") (pinfunction "DS_14") (pintype "input"))
      (node (ref "IC2") (pin "9") (pinfunction "Q7'_9") (pintype "tri_state"))
    )
    (net (code "32") (name "Net-(IC1A-Q7')") (class "Default")
      (node (ref "IC1") (pin "9") (pinfunction "Q7'_9") (pintype "tri_state"))
      (node (ref "IC7") (pin "14") (pinfunction "DS_14") (pintype "input"))
    )
    (net (code "33") (name "Net-(IC2A-Q0)") (class "Default")
      (node (ref "IC2") (pin "15") (pinfunction "Q0_15") (pintype "tri_state"))
      (node (ref "IC3") (pin "8") (pinfunction "I8_8") (pintype "input"))
    )
    (net (code "34") (name "Net-(IC2A-Q1)") (class "Default")
      (node (ref "IC2") (pin "1") (pinfunction "Q1_1") (pintype "tri_state"))
      (node (ref "IC3") (pin "7") (pinfunction "I7_7") (pintype "input"))
    )
    (net (code "35") (name "Net-(IC2A-Q2)") (class "Default")
      (node (ref "IC2") (pin "2") (pinfunction "Q2_2") (pintype "tri_state"))
      (node (ref "IC3") (pin "6") (pinfunction "I6_6") (pintype "input"))
    )
    (net (code "36") (name "Net-(IC2A-Q3)") (class "Default")
      (node (ref "IC2") (pin "3") (pinfunction "Q3_3") (pintype "tri_state"))
      (node (ref "IC3") (pin "5") (pinfunction "I5_5") (pintype "input"))
    )
    (net (code "37") (name "Net-(IC2A-Q4)") (class "Default")
      (node (ref "IC2") (pin "4") (pinfunction "Q4_4") (pintype "tri_state"))
      (node (ref "IC3") (pin "4") (pinfunction "I4_4") (pintype "input"))
    )
    (net (code "38") (name "Net-(IC2A-Q5)") (class "Default")
      (node (ref "IC2") (pin "5") (pinfunction "Q5_5") (pintype "tri_state"))
      (node (ref "IC3") (pin "3") (pinfunction "I3_3") (pintype "input"))
    )
    (net (code "39") (name "Net-(IC2A-Q6)") (class "Default")
      (node (ref "IC2") (pin "6") (pinfunction "Q6_6") (pintype "tri_state"))
      (node (ref "IC3") (pin "2") (pinfunction "I2_2") (pintype "input"))
    )
    (net (code "40") (name "Net-(IC2A-Q7)") (class "Default")
      (node (ref "IC2") (pin "7") (pinfunction "Q7_7") (pintype "tri_state"))
      (node (ref "IC3") (pin "1") (pinfunction "I1_1") (pintype "input"))
    )
    (net (code "41") (name "Net-(IC4-I1)") (class "Default")
      (node (ref "IC4") (pin "1") (pinfunction "I1_1") (pintype "input"))
      (node (ref "R49") (pin "1") (pinfunction "1_1") (pintype "passive"))
      (node (ref "R58") (pin "2") (pinfunction "2_2") (pintype "passive"))
    )
    (net (code "42") (name "Net-(IC4-I2)") (class "Default")
      (node (ref "IC4") (pin "2") (pinfunction "I2_2") (pintype "input"))
      (node (ref "R48") (pin "1") (pinfunction "1_1") (pintype "passive"))
      (node (ref "R57") (pin "2") (pinfunction "2_2") (pintype "passive"))
    )
    (net (code "43") (name "Net-(IC4-I3)") (class "Default")
      (node (ref "IC4") (pin "3") (pinfunction "I3_3") (pintype "input"))
      (node (ref "R47") (pin "1") (pinfunction "1_1") (pintype "passive"))
      (node (ref "R56") (pin "2") (pinfunction "2_2") (pintype "passive"))
    )
    (net (code "44") (name "Net-(IC4-I4)") (class "Default")
      (node (ref "IC4") (pin "4") (pinfunction "I4_4") (pintype "input"))
      (node (ref "R44") (pin "1") (pinfunction "1_1") (pintype "passive"))
      (node (ref "R55") (pin "2") (pinfunction "2_2") (pintype "passive"))
    )
    (net (code "45") (name "Net-(IC4-I5)") (class "Default")
      (node (ref "IC4") (pin "5") (pinfunction "I5_5") (pintype "input"))
      (node (ref "R43") (pin "1") (pinfunction "1_1") (pintype "passive"))
      (node (ref "R54") (pin "2") (pinfunction "2_2") (pintype "passive"))
    )
    (net (code "46") (name "Net-(IC4-I6)") (class "Default")
      (node (ref "IC4") (pin "6") (pinfunction "I6_6") (pintype "input"))
      (node (ref "R39") (pin "1") (pinfunction "1_1") (pintype "passive"))
      (node (ref "R53") (pin "2") (pinfunction "2_2") (pintype "passive"))
    )
    (net (code "47") (name "Net-(IC4-I7)") (class "Default")
      (node (ref "IC4") (pin "7") (pinfunction "I7_7") (pintype "input"))
      (node (ref "R1") (pin "1") (pinfunction "1_1") (pintype "passive"))
      (node (ref "R52") (pin "2") (pinfunction "2_2") (pintype "passive"))
    )
    (net (code "48") (name "Net-(IC4-I8)") (class "Default")
      (node (ref "IC4") (pin "8") (pinfunction "I8_8") (pintype "input"))
      (node (ref "R12") (pin "1") (pinfunction "1_1") (pintype "passive"))
      (node (ref "R51") (pin "2") (pinfunction "2_2") (pintype "passive"))
    )
    (net (code "49") (name "Net-(IC6-FB)") (class "Default")
      (node (ref "IC6") (pin "4") (pinfunction "FB_4") (pintype "input"))
      (node (ref "R2") (pin "2") (pinfunction "2_2") (pintype "passive"))
      (node (ref "R5") (pin "1") (pinfunction "1_1") (pintype "passive"))
    )
    (net (code "50") (name "Net-(IC6-OUT)") (class "Default")
      (node (ref "D5") (pin "C") (pinfunction "C_C") (pintype "passive"))
      (node (ref "IC6") (pin "2") (pinfunction "OUT_2") (pintype "output"))
      (node (ref "L1") (pin "2") (pinfunction "2_2") (pintype "passive"))
    )
    (net (code "51") (name "Net-(IC7A-Q6)") (class "Default")
      (node (ref "IC7") (pin "6") (pinfunction "Q6_6") (pintype "tri_state"))
      (node (ref "TR5") (pin "B") (pinfunction "B_B") (pintype "passive"))
    )
    (net (code "52") (name "Net-(IC7A-Q7)") (class "Default")
      (node (ref "IC7") (pin "7") (pinfunction "Q7_7") (pintype "tri_state"))
      (node (ref "TR4") (pin "B") (pinfunction "B_B") (pintype "passive"))
    )
    (net (code "53") (name "Net-(J1B-S)") (class "Default")
      (node (ref "J1") (pin "2") (pinfunction "S_2") (pintype "passive"))
      (node (ref "U1") (pin "6") (pinfunction "TXD_6") (pintype "bidirectional"))
      (node (ref "U3") (pin "P1") (pinfunction "GP1_P1") (pintype "bidirectional"))
    )
    (net (code "54") (name "Net-(J1C-S)") (class "Default")
      (node (ref "J1") (pin "3") (pinfunction "S_3") (pintype "passive"))
      (node (ref "U1") (pin "7") (pinfunction "RXD_7") (pintype "bidirectional"))
      (node (ref "U3") (pin "P0") (pinfunction "GP0_P0") (pintype "bidirectional"))
    )
    (net (code "55") (name "Net-(J2A-S)") (class "Default")
      (node (ref "J2") (pin "1") (pinfunction "S_1") (pintype "passive"))
      (node (ref "U3") (pin "P4") (pinfunction "GP4_P4") (pintype "bidirectional"))
    )
    (net (code "56") (name "Net-(J2B-S)") (class "Default")
      (node (ref "J2") (pin "2") (pinfunction "S_2") (pintype "passive"))
      (node (ref "U3") (pin "P5") (pinfunction "GP5_P5") (pintype "bidirectional"))
    )
    (net (code "57") (name "Net-(J4B-S)") (class "Default")
      (node (ref "J4") (pin "2") (pinfunction "S_2") (pintype "passive"))
      (node (ref "R45") (pin "2") (pinfunction "2_2") (pintype "passive"))
    )
    (net (code "58") (name "Net-(J4C-S)") (class "Default")
      (node (ref "J4") (pin "3") (pinfunction "S_3") (pintype "passive"))
      (node (ref "TR1") (pin "C") (pinfunction "C_C") (pintype "passive"))
    )
    (net (code "59") (name "Net-(J6B-S)") (class "Default")
      (node (ref "J6") (pin "2") (pinfunction "S_2") (pintype "passive"))
      (node (ref "R9") (pin "2") (pinfunction "2_2") (pintype "passive"))
      (node (ref "U3") (pin "P6") (pinfunction "GP6_P6") (pintype "bidirectional"))
    )
    (net (code "60") (name "Net-(J7B-S)") (class "Default")
      (node (ref "J7") (pin "2") (pinfunction "S_2") (pintype "passive"))
      (node (ref "Q9") (pin "5") (pinfunction "D1_5") (pintype "passive"))
      (node (ref "Q9") (pin "6") (pinfunction "D2_6") (pintype "passive"))
      (node (ref "Q9") (pin "7") (pinfunction "D2_7") (pintype "passive"))
      (node (ref "Q9") (pin "8") (pinfunction "D1_8") (pintype "passive"))
    )
    (net (code "61") (name "Net-(Q1A-D1)") (class "Default")
      (node (ref "Q1") (pin "7") (pinfunction "D2_7") (pintype "passive"))
      (node (ref "Q1") (pin "8") (pinfunction "D1_8") (pintype "passive"))
      (node (ref "X1") (pin "1") (pinfunction "S_1") (pintype "passive"))
    )
    (net (code "62") (name "Net-(Q1A-G)") (class "Default")
      (node (ref "Q1") (pin "2") (pinfunction "G_2") (pintype "passive"))
      (node (ref "R6") (pin "2") (pinfunction "2_2") (pintype "passive"))
      (node (ref "R7") (pin "1") (pinfunction "1_1") (pintype "passive"))
    )
    (net (code "63") (name "Net-(Q1B-D1)") (class "Default")
      (node (ref "Q1") (pin "5") (pinfunction "D1_5") (pintype "passive"))
      (node (ref "Q1") (pin "6") (pinfunction "D2_6") (pintype "passive"))
      (node (ref "X1") (pin "2") (pinfunction "S_2") (pintype "passive"))
    )
    (net (code "64") (name "Net-(Q1B-G)") (class "Default")
      (node (ref "Q1") (pin "4") (pinfunction "G_4") (pintype "passive"))
      (node (ref "R10") (pin "2") (pinfunction "2_2") (pintype "passive"))
      (node (ref "R14") (pin "1") (pinfunction "1_1") (pintype "passive"))
    )
    (net (code "65") (name "Net-(Q2A-D1)") (class "Default")
      (node (ref "Q2") (pin "7") (pinfunction "D2_7") (pintype "passive"))
      (node (ref "Q2") (pin "8") (pinfunction "D1_8") (pintype "passive"))
      (node (ref "X1") (pin "3") (pinfunction "S_3") (pintype "passive"))
    )
    (net (code "66") (name "Net-(Q2A-G)") (class "Default")
      (node (ref "Q2") (pin "2") (pinfunction "G_2") (pintype "passive"))
      (node (ref "R11") (pin "1") (pinfunction "1_1") (pintype "passive"))
      (node (ref "R13") (pin "2") (pinfunction "2_2") (pintype "passive"))
    )
    (net (code "67") (name "Net-(Q2B-D1)") (class "Default")
      (node (ref "Q2") (pin "5") (pinfunction "D1_5") (pintype "passive"))
      (node (ref "Q2") (pin "6") (pinfunction "D2_6") (pintype "passive"))
      (node (ref "X1") (pin "4") (pinfunction "S_4") (pintype "passive"))
    )
    (net (code "68") (name "Net-(Q2B-G)") (class "Default")
      (node (ref "Q2") (pin "4") (pinfunction "G_4") (pintype "passive"))
      (node (ref "R20") (pin "2") (pinfunction "2_2") (pintype "passive"))
      (node (ref "R21") (pin "1") (pinfunction "1_1") (pintype "passive"))
    )
    (net (code "69") (name "Net-(Q3A-D1)") (class "Default")
      (node (ref "Q3") (pin "7") (pinfunction "D2_7") (pintype "passive"))
      (node (ref "Q3") (pin "8") (pinfunction "D1_8") (pintype "passive"))
      (node (ref "X1") (pin "5") (pinfunction "S_5") (pintype "passive"))
    )
    (net (code "70") (name "Net-(Q3A-G)") (class "Default")
      (node (ref "Q3") (pin "2") (pinfunction "G_2") (pintype "passive"))
      (node (ref "R25") (pin "2") (pinfunction "2_2") (pintype "passive"))
      (node (ref "R26") (pin "1") (pinfunction "1_1") (pintype "passive"))
    )
    (net (code "71") (name "Net-(Q3B-D1)") (class "Default")
      (node (ref "Q3") (pin "5") (pinfunction "D1_5") (pintype "passive"))
      (node (ref "Q3") (pin "6") (pinfunction "D2_6") (pintype "passive"))
      (node (ref "X1") (pin "6") (pinfunction "S_6") (pintype "passive"))
    )
    (net (code "72") (name "Net-(Q3B-G)") (class "Default")
      (node (ref "Q3") (pin "4") (pinfunction "G_4") (pintype "passive"))
      (node (ref "R30") (pin "2") (pinfunction "2_2") (pintype "passive"))
      (node (ref "R31") (pin "1") (pinfunction "1_1") (pintype "passive"))
    )
    (net (code "73") (name "Net-(Q4A-D1)") (class "Default")
      (node (ref "Q4") (pin "7") (pinfunction "D2_7") (pintype "passive"))
      (node (ref "Q4") (pin "8") (pinfunction "D1_8") (pintype "passive"))
      (node (ref "X5") (pin "1") (pinfunction "S_1") (pintype "passive"))
    )
    (net (code "74") (name "Net-(Q4A-G)") (class "Default")
      (node (ref "Q4") (pin "2") (pinfunction "G_2") (pintype "passive"))
      (node (ref "R35") (pin "2") (pinfunction "2_2") (pintype "passive"))
      (node (ref "R36") (pin "1") (pinfunction "1_1") (pintype "passive"))
    )
    (net (code "75") (name "Net-(Q4B-D1)") (class "Default")
      (node (ref "Q4") (pin "5") (pinfunction "D1_5") (pintype "passive"))
      (node (ref "Q4") (pin "6") (pinfunction "D2_6") (pintype "passive"))
      (node (ref "X5") (pin "2") (pinfunction "S_2") (pintype "passive"))
    )
    (net (code "76") (name "Net-(Q4B-G)") (class "Default")
      (node (ref "Q4") (pin "4") (pinfunction "G_4") (pintype "passive"))
      (node (ref "R38") (pin "2") (pinfunction "2_2") (pintype "passive"))
      (node (ref "R41") (pin "1") (pinfunction "1_1") (pintype "passive"))
    )
    (net (code "77") (name "Net-(Q5A-D1)") (class "Default")
      (node (ref "Q5") (pin "7") (pinfunction "D2_7") (pintype "passive"))
      (node (ref "Q5") (pin "8") (pinfunction "D1_8") (pintype "passive"))
      (node (ref "X3") (pin "1") (pinfunction "S_1") (pintype "passive"))
    )
    (net (code "78") (name "Net-(Q5A-G)") (class "Default")
      (node (ref "Q5") (pin "2") (pinfunction "G_2") (pintype "passive"))
      (node (ref "R8") (pin "1") (pinfunction "1_1") (pintype "passive"))
    )
    (net (code "79") (name "Net-(Q5B-D1)") (class "Default")
      (node (ref "Q5") (pin "5") (pinfunction "D1_5") (pintype "passive"))
      (node (ref "Q5") (pin "6") (pinfunction "D2_6") (pintype "passive"))
      (node (ref "X3") (pin "2") (pinfunction "S_2") (pintype "passive"))
    )
    (net (code "80") (name "Net-(Q5B-G)") (class "Default")
      (node (ref "Q5") (pin "4") (pinfunction "G_4") (pintype "passive"))
      (node (ref "R15") (pin "1") (pinfunction "1_1") (pintype "passive"))
    )
    (net (code "81") (name "Net-(Q6A-D1)") (class "Default")
      (node (ref "Q6") (pin "7") (pinfunction "D2_7") (pintype "passive"))
      (node (ref "Q6") (pin "8") (pinfunction "D1_8") (pintype "passive"))
      (node (ref "X3") (pin "3") (pinfunction "S_3") (pintype "passive"))
    )
    (net (code "82") (name "Net-(Q6A-G)") (class "Default")
      (node (ref "Q6") (pin "2") (pinfunction "G_2") (pintype "passive"))
      (node (ref "R17") (pin "1") (pinfunction "1_1") (pintype "passive"))
    )
    (net (code "83") (name "Net-(Q6B-D1)") (class "Default")
      (node (ref "Q6") (pin "5") (pinfunction "D1_5") (pintype "passive"))
      (node (ref "Q6") (pin "6") (pinfunction "D2_6") (pintype "passive"))
      (node (ref "X3") (pin "4") (pinfunction "S_4") (pintype "passive"))
    )
    (net (code "84") (name "Net-(Q6B-G)") (class "Default")
      (node (ref "Q6") (pin "4") (pinfunction "G_4") (pintype "passive"))
      (node (ref "R22") (pin "1") (pinfunction "1_1") (pintype "passive"))
    )
    (net (code "85") (name "Net-(Q7A-D1)") (class "Default")
      (node (ref "Q7") (pin "7") (pinfunction "D2_7") (pintype "passive"))
      (node (ref "Q7") (pin "8") (pinfunction "D1_8") (pintype "passive"))
      (node (ref "X3") (pin "5") (pinfunction "S_5") (pintype "passive"))
    )
    (net (code "86") (name "Net-(Q7A-G)") (class "Default")
      (node (ref "Q7") (pin "2") (pinfunction "G_2") (pintype "passive"))
      (node (ref "R27") (pin "1") (pinfunction "1_1") (pintype "passive"))
    )
    (net (code "87") (name "Net-(Q7B-D1)") (class "Default")
      (node (ref "Q7") (pin "5") (pinfunction "D1_5") (pintype "passive"))
      (node (ref "Q7") (pin "6") (pinfunction "D2_6") (pintype "passive"))
      (node (ref "X3") (pin "6") (pinfunction "S_6") (pintype "passive"))
    )
    (net (code "88") (name "Net-(Q7B-G)") (class "Default")
      (node (ref "Q7") (pin "4") (pinfunction "G_4") (pintype "passive"))
      (node (ref "R32") (pin "1") (pinfunction "1_1") (pintype "passive"))
    )
    (net (code "89") (name "Net-(Q8A-D1)") (class "Default")
      (node (ref "Q8") (pin "7") (pinfunction "D2_7") (pintype "passive"))
      (node (ref "Q8") (pin "8") (pinfunction "D1_8") (pintype "passive"))
      (node (ref "X4") (pin "1") (pinfunction "S_1") (pintype "passive"))
    )
    (net (code "90") (name "Net-(Q8A-G)") (class "Default")
      (node (ref "Q8") (pin "2") (pinfunction "G_2") (pintype "passive"))
      (node (ref "R37") (pin "1") (pinfunction "1_1") (pintype "passive"))
    )
    (net (code "91") (name "Net-(Q8B-D1)") (class "Default")
      (node (ref "Q8") (pin "5") (pinfunction "D1_5") (pintype "passive"))
      (node (ref "Q8") (pin "6") (pinfunction "D2_6") (pintype "passive"))
      (node (ref "X4") (pin "2") (pinfunction "S_2") (pintype "passive"))
    )
    (net (code "92") (name "Net-(Q8B-G)") (class "Default")
      (node (ref "Q8") (pin "4") (pinfunction "G_4") (pintype "passive"))
      (node (ref "R42") (pin "1") (pinfunction "1_1") (pintype "passive"))
    )
    (net (code "93") (name "Net-(Q9A-G)") (class "Default")
      (node (ref "Q9") (pin "2") (pinfunction "G_2") (pintype "passive"))
      (node (ref "Q9") (pin "4") (pinfunction "G_4") (pintype "passive"))
      (node (ref "R18") (pin "2") (pinfunction "2_2") (pintype "passive"))
    )
    (net (code "94") (name "Net-(Q10A-D1)") (class "Default")
      (node (ref "Q10") (pin "7") (pinfunction "D2_7") (pintype "passive"))
      (node (ref "Q10") (pin "8") (pinfunction "D1_8") (pintype "passive"))
      (node (ref "X4") (pin "3") (pinfunction "S_3") (pintype "passive"))
    )
    (net (code "95") (name "Net-(Q10A-G)") (class "Default")
      (node (ref "Q10") (pin "2") (pinfunction "G_2") (pintype "passive"))
      (node (ref "R50") (pin "1") (pinfunction "1_1") (pintype "passive"))
    )
    (net (code "96") (name "Net-(Q10B-D1)") (class "Default")
      (node (ref "Q10") (pin "5") (pinfunction "D1_5") (pintype "passive"))
      (node (ref "Q10") (pin "6") (pinfunction "D2_6") (pintype "passive"))
      (node (ref "X4") (pin "4") (pinfunction "S_4") (pintype "passive"))
    )
    (net (code "97") (name "Net-(Q10B-G)") (class "Default")
      (node (ref "Q10") (pin "4") (pinfunction "G_4") (pintype "passive"))
      (node (ref "R40") (pin "1") (pinfunction "1_1") (pintype "passive"))
    )
    (net (code "98") (name "Net-(Q11A-D1)") (class "Default")
      (node (ref "Q11") (pin "7") (pinfunction "D2_7") (pintype "passive"))
      (node (ref "Q11") (pin "8") (pinfunction "D1_8") (pintype "passive"))
      (node (ref "X5") (pin "3") (pinfunction "S_3") (pintype "passive"))
    )
    (net (code "99") (name "Net-(Q11A-G)") (class "Default")
      (node (ref "Q11") (pin "2") (pinfunction "G_2") (pintype "passive"))
      (node (ref "R19") (pin "1") (pinfunction "1_1") (pintype "passive"))
      (node (ref "R23") (pin "2") (pinfunction "2_2") (pintype "passive"))
    )
    (net (code "100") (name "Net-(Q11B-D1)") (class "Default")
      (node (ref "Q11") (pin "5") (pinfunction "D1_5") (pintype "passive"))
      (node (ref "Q11") (pin "6") (pinfunction "D2_6") (pintype "passive"))
      (node (ref "X5") (pin "4") (pinfunction "S_4") (pintype "passive"))
    )
    (net (code "101") (name "Net-(Q11B-G)") (class "Default")
      (node (ref "Q11") (pin "4") (pinfunction "G_4") (pintype "passive"))
      (node (ref "R29") (pin "1") (pinfunction "1_1") (pintype "passive"))
      (node (ref "R33") (pin "2") (pinfunction "2_2") (pintype "passive"))
    )
    (net (code "102") (name "Net-(R3-Pad1)") (class "Default")
      (node (ref "R3") (pin "1") (pinfunction "1_1") (pintype "passive"))
      (node (ref "TR1") (pin "B") (pinfunction "B_B") (pintype "passive"))
    )
    (net (code "103") (name "Net-(R16-Pad2)") (class "Default")
      (node (ref "R16") (pin "2") (pinfunction "2_2") (pintype "passive"))
      (node (ref "R3") (pin "2") (pinfunction "2_2") (pintype "passive"))
      (node (ref "TR2") (pin "C") (pinfunction "C_C") (pintype "passive"))
    )
    (net (code "104") (name "Net-(R28-Pad1)") (class "Default")
      (node (ref "R28") (pin "1") (pinfunction "1_1") (pintype "passive"))
      (node (ref "TR2") (pin "B") (pinfunction "B_B") (pintype "passive"))
    )
    (net (code "105") (name "Net-(R45-Pad1)") (class "Default")
      (node (ref "R45") (pin "1") (pinfunction "1_1") (pintype "passive"))
      (node (ref "TR3") (pin "B") (pinfunction "B_B") (pintype "passive"))
    )
    (net (code "106") (name "Net-(U1-UD+)") (class "Default")
      (node (ref "U$3") (pin "D+") (pinfunction "D+_D+") (pintype "bidirectional"))
      (node (ref "U1") (pin "1") (pinfunction "UD+_1") (pintype "bidirectional"))
    )
    (net (code "107") (name "Net-(U1-UD-)") (class "Default")
      (node (ref "U$3") (pin "D-") (pinfunction "D-_D-") (pintype "bidirectional"))
      (node (ref "U1") (pin "2") (pinfunction "UD-_2") (pintype "bidirectional"))
    )
    (net (code "108") (name "Net-(U1-V3)") (class "Default")
      (node (ref "C1") (pin "1") (pinfunction "1_1") (pintype "passive"))
      (node (ref "U1") (pin "8") (pinfunction "V3_8") (pintype "bidirectional"))
    )
    (net (code "109") (name "Net-(U1-VCC)") (class "Default")
      (node (ref "C10") (pin "1") (pinfunction "1_1") (pintype "passive"))
      (node (ref "U1") (pin "5") (pinfunction "VCC_5") (pintype "power_in"))
      (node (ref "U3") (pin "3V3") (pinfunction "3V3_3V3") (pintype "power_in"))
    )
    (net (code "110") (name "Net-(U3-GP2)") (class "Default")
      (node (ref "R28") (pin "2") (pinfunction "2_2") (pintype "passive"))
      (node (ref "U3") (pin "P2") (pinfunction "GP2_P2") (pintype "bidirectional"))
    )
    (net (code "111") (name "Net-(U3-GP3)") (class "Default")
      (node (ref "R46") (pin "2") (pinfunction "2_2") (pintype "passive"))
      (node (ref "TR3") (pin "E") (pinfunction "E_E") (pintype "passive"))
      (node (ref "U3") (pin "P3") (pinfunction "GP3_P3") (pintype "bidirectional"))
    )
    (net (code "112") (name "Net-(U3-GP7)") (class "Default")
      (node (ref "R18") (pin "1") (pinfunction "1_1") (pintype "passive"))
      (node (ref "U3") (pin "P7") (pinfunction "GP7_P7") (pintype "bidirectional"))
    )
    (net (code "113") (name "Net-(U3-GP12)") (class "Default")
      (node (ref "U3") (pin "P12") (pinfunction "GP12_P12") (pintype "bidirectional"))
      (node (ref "X7") (pin "1") (pinfunction "S_1") (pintype "passive"))
    )
    (net (code "114") (name "Net-(U3-GP13)") (class "Default")
      (node (ref "U3") (pin "P13") (pinfunction "GP13_P13") (pintype "bidirectional"))
      (node (ref "X7") (pin "2") (pinfunction "S_2") (pintype "passive"))
    )
    (net (code "115") (name "Net-(U3-GP14)") (class "Default")
      (node (ref "U3") (pin "P14") (pinfunction "GP14_P14") (pintype "bidirectional"))
      (node (ref "X7") (pin "3") (pinfunction "S_3") (pintype "passive"))
    )
    (net (code "116") (name "Net-(U3-GP15)") (class "Default")
      (node (ref "U3") (pin "P15") (pinfunction "GP15_P15") (pintype "bidirectional"))
      (node (ref "X7") (pin "4") (pinfunction "S_4") (pintype "passive"))
    )
    (net (code "117") (name "Net-(U3-GP26)") (class "Default")
      (node (ref "U3") (pin "P26") (pinfunction "GP26_P26") (pintype "bidirectional"))
      (node (ref "X8") (pin "1") (pinfunction "S_1") (pintype "passive"))
    )
    (net (code "118") (name "Net-(U3-GP27)") (class "Default")
      (node (ref "U3") (pin "P27") (pinfunction "GP27_P27") (pintype "bidirectional"))
      (node (ref "X8") (pin "2") (pinfunction "S_2") (pintype "passive"))
    )
    (net (code "119") (name "Net-(U3-GP28)") (class "Default")
      (node (ref "U3") (pin "P28") (pinfunction "GP28_P28") (pintype "bidirectional"))
      (node (ref "X8") (pin "3") (pinfunction "S_3") (pintype "passive"))
    )
    (net (code "120") (name "Net-(U3-GP29)") (class "Default")
      (node (ref "U3") (pin "P29") (pinfunction "GP29_P29") (pintype "bidirectional"))
      (node (ref "X8") (pin "4") (pinfunction "S_4") (pintype "passive"))
    )
    (net (code "121") (name "Net-(X2A-S)") (class "Default")
      (node (ref "R49") (pin "2") (pinfunction "2_2") (pintype "passive"))
      (node (ref "X2") (pin "1") (pinfunction "S_1") (pintype "passive"))
    )
    (net (code "122") (name "Net-(X2B-S)") (class "Default")
      (node (ref "R48") (pin "2") (pinfunction "2_2") (pintype "passive"))
      (node (ref "X2") (pin "2") (pinfunction "S_2") (pintype "passive"))
    )
    (net (code "123") (name "Net-(X2C-S)") (class "Default")
      (node (ref "R47") (pin "2") (pinfunction "2_2") (pintype "passive"))
      (node (ref "X2") (pin "3") (pinfunction "S_3") (pintype "passive"))
    )
    (net (code "124") (name "Net-(X2D-S)") (class "Default")
      (node (ref "R44") (pin "2") (pinfunction "2_2") (pintype "passive"))
      (node (ref "X2") (pin "4") (pinfunction "S_4") (pintype "passive"))
    )
    (net (code "125") (name "Net-(X2E-S)") (class "Default")
      (node (ref "R43") (pin "2") (pinfunction "2_2") (pintype "passive"))
      (node (ref "X2") (pin "5") (pinfunction "S_5") (pintype "passive"))
    )
    (net (code "126") (name "Net-(X2F-S)") (class "Default")
      (node (ref "R39") (pin "2") (pinfunction "2_2") (pintype "passive"))
      (node (ref "X2") (pin "6") (pinfunction "S_6") (pintype "passive"))
    )
    (net (code "127") (name "Net-(X2G-S)") (class "Default")
      (node (ref "R1") (pin "2") (pinfunction "2_2") (pintype "passive"))
      (node (ref "X2") (pin "7") (pinfunction "S_7") (pintype "passive"))
    )
    (net (code "128") (name "Net-(X2H-S)") (class "Default")
      (node (ref "R12") (pin "2") (pinfunction "2_2") (pintype "passive"))
      (node (ref "X2") (pin "8") (pinfunction "S_8") (pintype "passive"))
    )
    (net (code "129") (name "Net-(X6B-S)") (class "Default")
      (node (ref "D1") (pin "A") (pinfunction "A_A") (pintype "passive"))
      (node (ref "J3") (pin "3") (pinfunction "3_3") (pintype "passive"))
      (node (ref "X6") (pin "2") (pinfunction "S_2") (pintype "passive"))
    )
    (net (code "130") (name "SH_CP") (class "Default")
      (node (ref "IC1") (pin "11") (pinfunction "SH_CK_11") (pintype "input"))
      (node (ref "IC2") (pin "11") (pinfunction "SH_CK_11") (pintype "input"))
      (node (ref "IC7") (pin "11") (pinfunction "SH_CK_11") (pintype "input"))
      (node (ref "U3") (pin "P10") (pinfunction "GP10_P10") (pintype "bidirectional"))
    )
    (net (code "131") (name "ST_CP") (class "Default")
      (node (ref "IC1") (pin "12") (pinfunction "ST_CK_12") (pintype "input"))
      (node (ref "IC2") (pin "12") (pinfunction "ST_CK_12") (pintype "input"))
      (node (ref "IC7") (pin "12") (pinfunction "ST_CK_12") (pintype "input"))
      (node (ref "U3") (pin "P9") (pinfunction "GP9_P9") (pintype "bidirectional"))
    )
    (net (code "132") (name "VCC") (class "Default")
      (node (ref "R16") (pin "1") (pinfunction "1_1") (pintype "passive"))
      (node (ref "R24") (pin "1") (pinfunction "1_1") (pintype "passive"))
      (node (ref "TR1") (pin "E") (pinfunction "E_E") (pintype "passive"))
    )
    (net (code "133") (name "unconnected-(IC3-CD+-Pad10)") (class "Default")
      (node (ref "IC3") (pin "10") (pinfunction "CD+_10") (pintype "passive"))
    )
    (net (code "134") (name "unconnected-(IC4-CD+-Pad10)") (class "Default")
      (node (ref "IC4") (pin "10") (pinfunction "CD+_10") (pintype "passive"))
    )
    (net (code "135") (name "unconnected-(IC6-~{ON}{slash}OFF-Pad5)") (class "Default")
      (node (ref "IC6") (pin "5") (pinfunction "~{ON}/OFF_5") (pintype "input"))
    )
    (net (code "136") (name "unconnected-(IC7A-Q2-Pad2)") (class "Default")
      (node (ref "IC7") (pin "2") (pinfunction "Q2_2") (pintype "tri_state"))
    )
    (net (code "137") (name "unconnected-(IC7A-Q3-Pad3)") (class "Default")
      (node (ref "IC7") (pin "3") (pinfunction "Q3_3") (pintype "tri_state"))
    )
    (net (code "138") (name "unconnected-(IC7A-Q4-Pad4)") (class "Default")
      (node (ref "IC7") (pin "4") (pinfunction "Q4_4") (pintype "tri_state"))
    )
    (net (code "139") (name "unconnected-(IC7A-Q5-Pad5)") (class "Default")
      (node (ref "IC7") (pin "5") (pinfunction "Q5_5") (pintype "tri_state"))
    )
    (net (code "140") (name "unconnected-(IC7A-Q7'-Pad9)") (class "Default")
      (node (ref "IC7") (pin "9") (pinfunction "Q7'_9") (pintype "tri_state"))
    )
    (net (code "141") (name "unconnected-(J3-Pad2)") (class "Default")
      (node (ref "J3") (pin "2") (pinfunction "2_2") (pintype "passive"))
    )
    (net (code "142") (name "unconnected-(U$3-VBUS-PadV)") (class "Default")
      (node (ref "U$3") (pin "V") (pinfunction "VBUS_V") (pintype "bidirectional"))
    )
    (net (code "143") (name "unconnected-(U1-RTS#-Pad4)") (class "Default")
      (node (ref "U1") (pin "4") (pinfunction "RTS#_4") (pintype "bidirectional"))
    )
    (net (code "144") (name "unconnected-(U3-GP17-PadP17)") (class "Default")
      (node (ref "U3") (pin "P17") (pinfunction "GP17_P17") (pintype "bidirectional"))
    )
    (net (code "145") (name "unconnected-(U3-GP18-PadP18)") (class "Default")
      (node (ref "U3") (pin "P18") (pinfunction "GP18_P18") (pintype "bidirectional"))
    )
    (net (code "146") (name "unconnected-(U3-GP19-PadP19)") (class "Default")
      (node (ref "U3") (pin "P19") (pinfunction "GP19_P19") (pintype "bidirectional"))
    )
    (net (code "147") (name "unconnected-(U3-GP20-PadP20)") (class "Default")
      (node (ref "U3") (pin "P20") (pinfunction "GP20_P20") (pintype "bidirectional"))
    )
    (net (code "148") (name "unconnected-(U3-GP21-PadP21)") (class "Default")
      (node (ref "U3") (pin "P21") (pinfunction "GP21_P21") (pintype "bidirectional"))
    )
    (net (code "149") (name "unconnected-(U3-GP22-PadP22)") (class "Default")
      (node (ref "U3") (pin "P22") (pinfunction "GP22_P22") (pintype "bidirectional"))
    )
    (net (code "150") (name "unconnected-(U3-GP23-PadP23)") (class "Default")
      (node (ref "U3") (pin "P23") (pinfunction "GP23_P23") (pintype "bidirectional"))
    )
    (net (code "151") (name "unconnected-(U3-GP24-PadP24)") (class "Default")
      (node (ref "U3") (pin "P24") (pinfunction "GP24_P24") (pintype "bidirectional"))
    )
    (net (code "152") (name "unconnected-(U3-GP25-PadP25)") (class "Default")
      (node (ref "U3") (pin "P25") (pinfunction "GP25_P25") (pintype "bidirectional"))
    )
  )
)
